# bt_bio.net
KiCad netlist of a schematic drawn in EAGLE
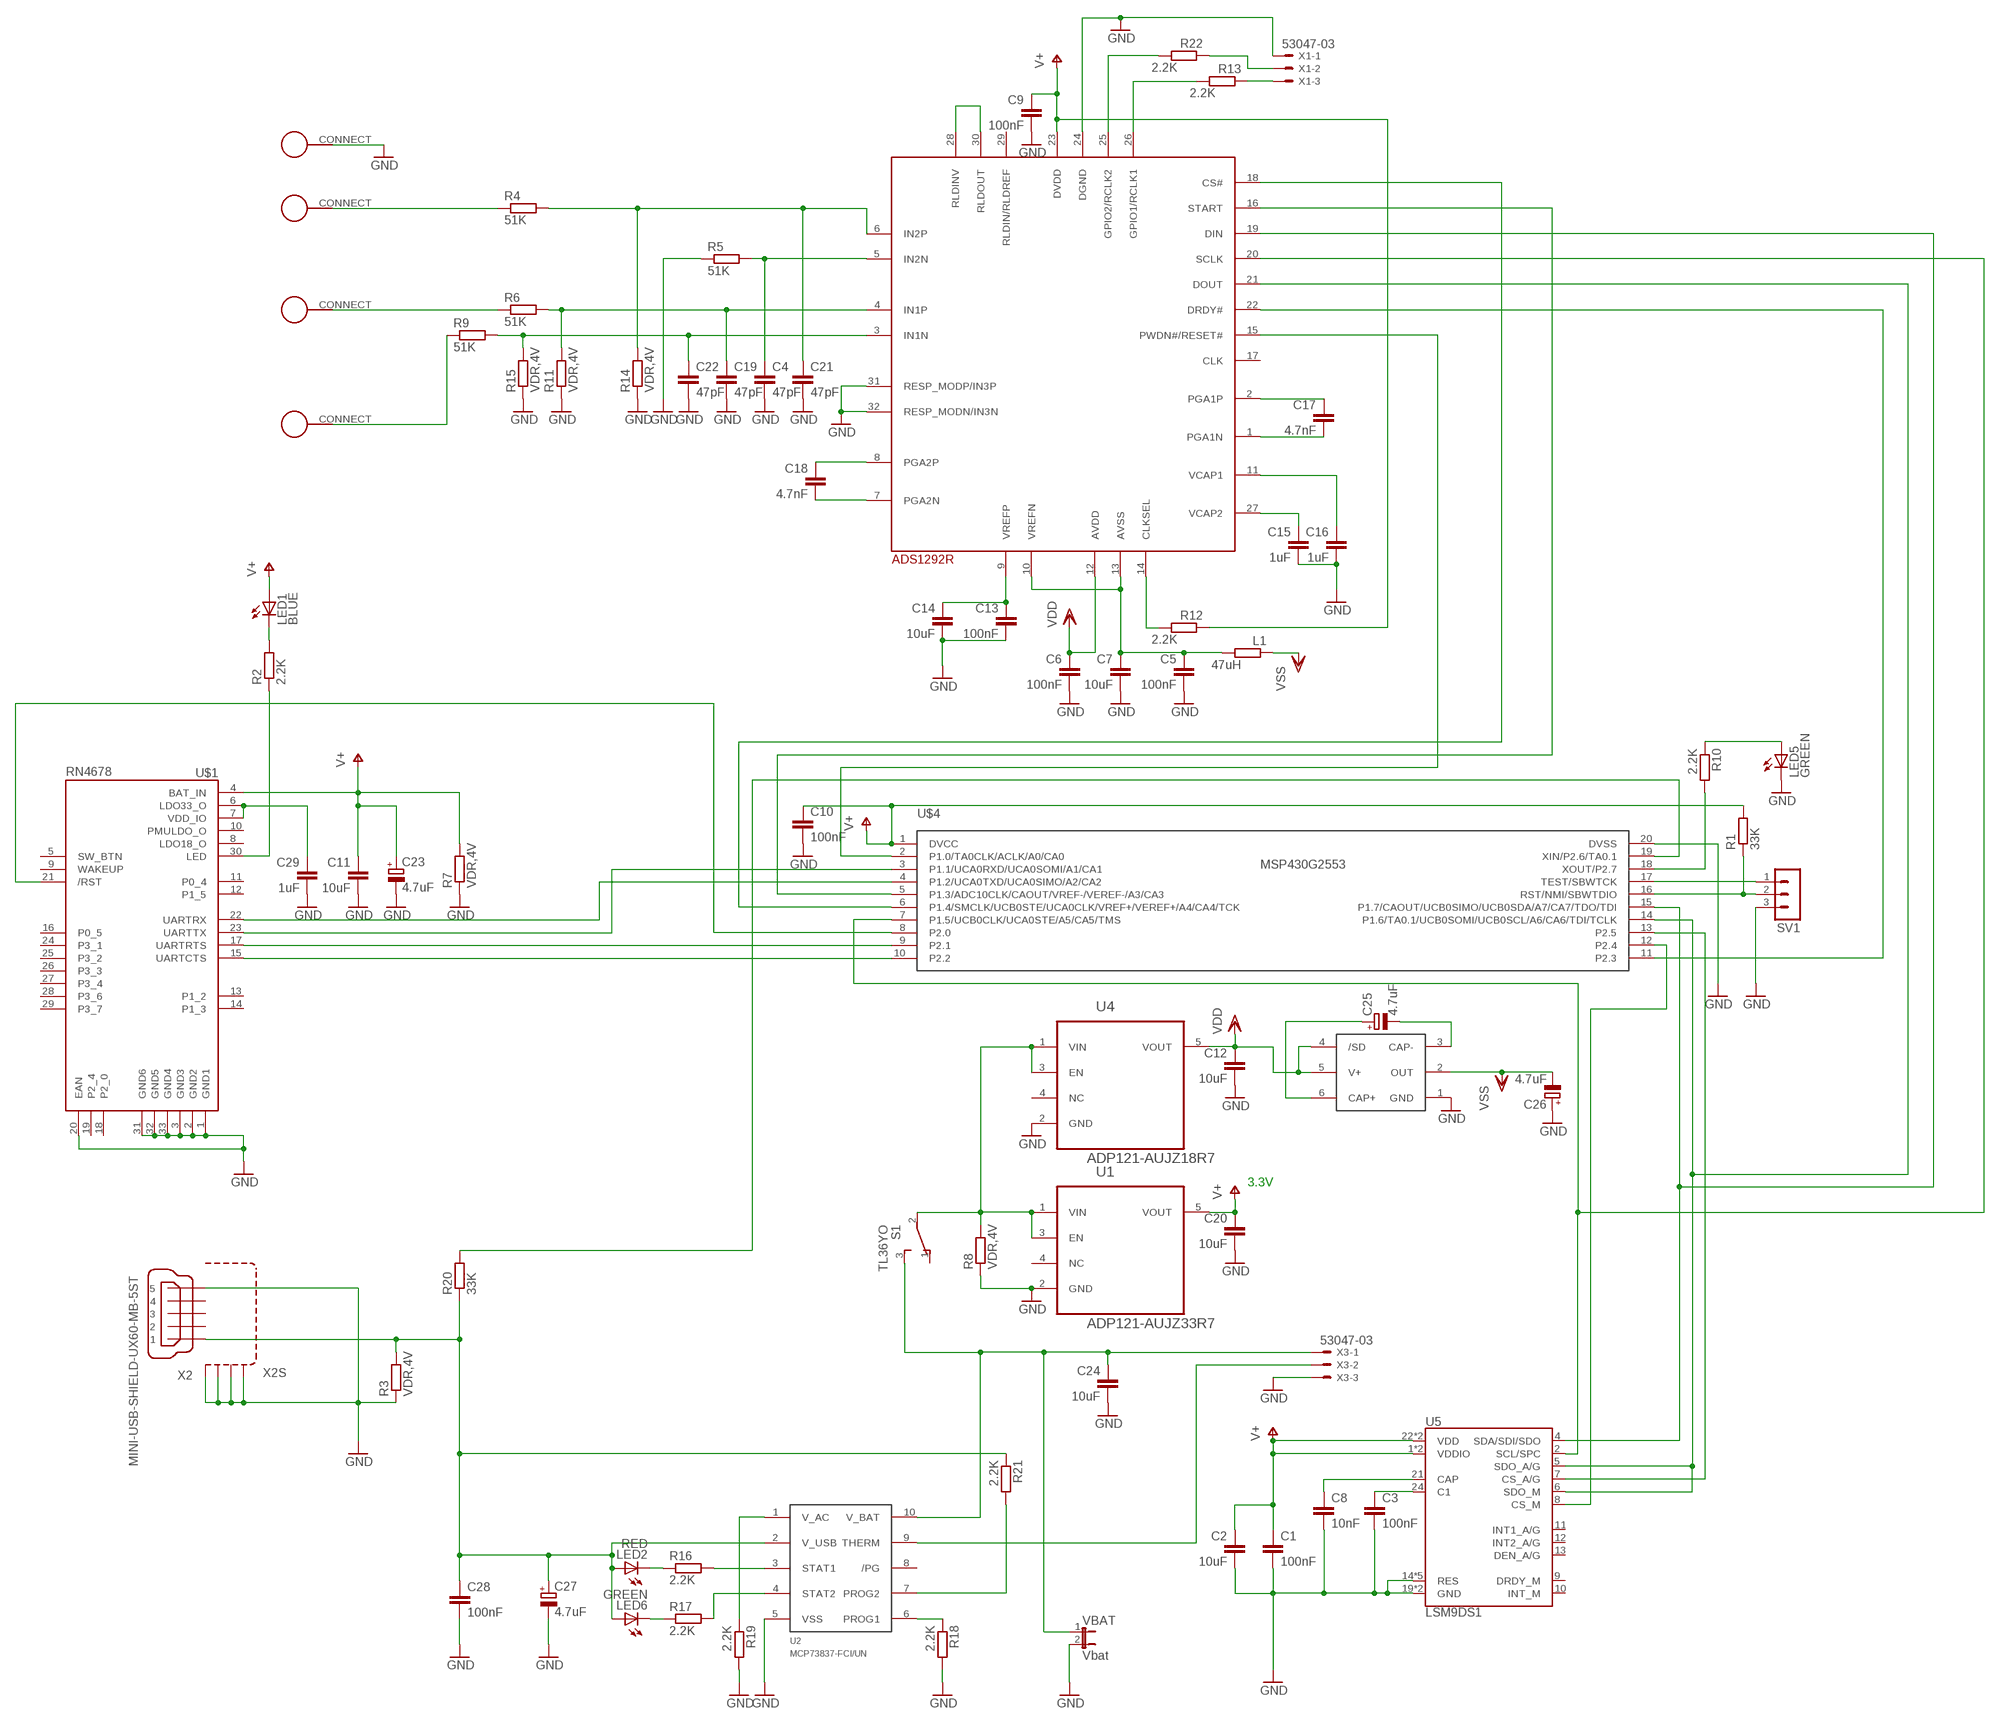
[diagram p0: schematic, sheet 1]

(export (version "E")
  (design (tool "Eeschema 10.0.6"))
  (components
    (comp (ref "ADS1292R")
      (value "ADS1292R")
      (footprint "eagle-import:TQFP-32")
      (libsource (lib "eagle-import") (part "ADS1292R"))
    )
    (comp (ref "C1")
      (value "100nF")
      (footprint "eagle-import:C0603")
      (libsource (lib "eagle-import") (part "C-EUC0603"))
    )
    (comp (ref "C2")
      (value "10uF")
      (footprint "eagle-import:C1206")
      (libsource (lib "eagle-import") (part "C-EUC1206"))
    )
    (comp (ref "C3")
      (value "100nF")
      (footprint "eagle-import:C0603")
      (libsource (lib "eagle-import") (part "C-EUC0603"))
    )
    (comp (ref "C4")
      (value "47pF")
      (footprint "eagle-import:C0603")
      (libsource (lib "eagle-import") (part "C-EUC0603"))
    )
    (comp (ref "C5")
      (value "100nF")
      (footprint "eagle-import:C0603")
      (libsource (lib "eagle-import") (part "C-EUC0603"))
    )
    (comp (ref "C6")
      (value "100nF")
      (footprint "eagle-import:C0603")
      (libsource (lib "eagle-import") (part "C-EUC0603"))
    )
    (comp (ref "C7")
      (value "10uF")
      (footprint "eagle-import:C1206")
      (libsource (lib "eagle-import") (part "C-EUC1206"))
    )
    (comp (ref "C8")
      (value "10nF")
      (footprint "eagle-import:C0603")
      (libsource (lib "eagle-import") (part "C-EUC0603"))
    )
    (comp (ref "C9")
      (value "100nF")
      (footprint "eagle-import:C0603")
      (libsource (lib "eagle-import") (part "C-EUC0603"))
    )
    (comp (ref "C10")
      (value "100nF")
      (footprint "eagle-import:C0603")
      (libsource (lib "eagle-import") (part "C-EUC0603"))
    )
    (comp (ref "C11")
      (value "10uF")
      (footprint "eagle-import:C1206")
      (libsource (lib "eagle-import") (part "C-EUC1206"))
    )
    (comp (ref "C12")
      (value "10uF")
      (footprint "eagle-import:C1206")
      (libsource (lib "eagle-import") (part "C-EUC1206"))
    )
    (comp (ref "C13")
      (value "100nF")
      (footprint "eagle-import:C0603")
      (libsource (lib "eagle-import") (part "C-EUC0603"))
    )
    (comp (ref "C14")
      (value "10uF")
      (footprint "eagle-import:C1206")
      (libsource (lib "eagle-import") (part "C-EUC1206"))
    )
    (comp (ref "C15")
      (value "1uF")
      (footprint "eagle-import:C0603")
      (libsource (lib "eagle-import") (part "C-EUC0603"))
    )
    (comp (ref "C16")
      (value "1uF")
      (footprint "eagle-import:C0603")
      (libsource (lib "eagle-import") (part "C-EUC0603"))
    )
    (comp (ref "C17")
      (value "4.7nF")
      (footprint "eagle-import:C0603")
      (libsource (lib "eagle-import") (part "C-EUC0603"))
    )
    (comp (ref "C18")
      (value "4.7nF")
      (footprint "eagle-import:C0603")
      (libsource (lib "eagle-import") (part "C-EUC0603"))
    )
    (comp (ref "C19")
      (value "47pF")
      (footprint "eagle-import:C0603")
      (libsource (lib "eagle-import") (part "C-EUC0603"))
    )
    (comp (ref "C20")
      (value "10uF")
      (footprint "eagle-import:C1206")
      (libsource (lib "eagle-import") (part "C-EUC1206"))
    )
    (comp (ref "C21")
      (value "47pF")
      (footprint "eagle-import:C0603")
      (libsource (lib "eagle-import") (part "C-EUC0603"))
    )
    (comp (ref "C22")
      (value "47pF")
      (footprint "eagle-import:C0603")
      (libsource (lib "eagle-import") (part "C-EUC0603"))
    )
    (comp (ref "C23")
      (value "4.7uF")
      (footprint "eagle-import:SMC_C")
      (libsource (lib "eagle-import") (part "CPOL-EUSMCC"))
    )
    (comp (ref "C24")
      (value "10uF")
      (footprint "eagle-import:C1206")
      (libsource (lib "eagle-import") (part "C-EUC1206"))
    )
    (comp (ref "C25")
      (value "4.7uF")
      (footprint "eagle-import:SMC_C")
      (libsource (lib "eagle-import") (part "CPOL-EUSMCC"))
    )
    (comp (ref "C26")
      (value "4.7uF")
      (footprint "eagle-import:SMC_C")
      (libsource (lib "eagle-import") (part "CPOL-EUSMCC"))
    )
    (comp (ref "C27")
      (value "4.7uF")
      (footprint "eagle-import:SMC_C")
      (libsource (lib "eagle-import") (part "CPOL-EUSMCC"))
    )
    (comp (ref "C28")
      (value "100nF")
      (footprint "eagle-import:C0603")
      (libsource (lib "eagle-import") (part "C-EUC0603"))
    )
    (comp (ref "C29")
      (value "1uF")
      (footprint "eagle-import:C0603")
      (libsource (lib "eagle-import") (part "C-EUC0603"))
    )
    (comp (ref "L1")
      (value "47uH")
      (footprint "eagle-import:R0805")
      (libsource (lib "eagle-import") (part "R-EU_R0805"))
    )
    (comp (ref "LED1")
      (value "BLUE")
      (footprint "eagle-import:CHIPLED_0805")
      (libsource (lib "eagle-import") (part "LEDCHIPLED_0805"))
    )
    (comp (ref "LED2")
      (value "RED")
      (footprint "eagle-import:CHIPLED_0805")
      (libsource (lib "eagle-import") (part "LEDCHIPLED_0805"))
    )
    (comp (ref "LED5")
      (value "GREEN")
      (footprint "eagle-import:CHIPLED_0805")
      (libsource (lib "eagle-import") (part "LEDCHIPLED_0805"))
    )
    (comp (ref "LED6")
      (value "GREEN")
      (footprint "eagle-import:CHIPLED_0805")
      (libsource (lib "eagle-import") (part "LEDCHIPLED_0805"))
    )
    (comp (ref "R1")
      (value "33K")
      (footprint "eagle-import:R0603")
      (libsource (lib "eagle-import") (part "resistor_R-EU_R0603"))
    )
    (comp (ref "R2")
      (value "2.2K")
      (footprint "eagle-import:R0603")
      (libsource (lib "eagle-import") (part "R-EU_R0603"))
    )
    (comp (ref "R3")
      (value "VDR,4V")
      (footprint "eagle-import:R0805")
      (libsource (lib "eagle-import") (part "R-EU_R0805"))
    )
    (comp (ref "R4")
      (value "51K")
      (footprint "eagle-import:R0603")
      (libsource (lib "eagle-import") (part "R-EU_R0603"))
    )
    (comp (ref "R5")
      (value "51K")
      (footprint "eagle-import:R0603")
      (libsource (lib "eagle-import") (part "R-EU_R0603"))
    )
    (comp (ref "R6")
      (value "51K")
      (footprint "eagle-import:R0603")
      (libsource (lib "eagle-import") (part "R-EU_R0603"))
    )
    (comp (ref "R7")
      (value "VDR,4V")
      (footprint "eagle-import:R0805")
      (libsource (lib "eagle-import") (part "R-EU_R0805"))
    )
    (comp (ref "R8")
      (value "VDR,4V")
      (footprint "eagle-import:R0805")
      (libsource (lib "eagle-import") (part "R-EU_R0805"))
    )
    (comp (ref "R9")
      (value "51K")
      (footprint "eagle-import:R0603")
      (libsource (lib "eagle-import") (part "R-EU_R0603"))
    )
    (comp (ref "R10")
      (value "2.2K")
      (footprint "eagle-import:R0603")
      (libsource (lib "eagle-import") (part "R-EU_R0603"))
    )
    (comp (ref "R11")
      (value "VDR,4V")
      (footprint "eagle-import:R0805")
      (libsource (lib "eagle-import") (part "R-EU_R0805"))
    )
    (comp (ref "R12")
      (value "2.2K")
      (footprint "eagle-import:R0603")
      (libsource (lib "eagle-import") (part "R-EU_R0603"))
    )
    (comp (ref "R13")
      (value "2.2K")
      (footprint "eagle-import:R0603")
      (libsource (lib "eagle-import") (part "R-EU_R0603"))
    )
    (comp (ref "R14")
      (value "VDR,4V")
      (footprint "eagle-import:R0805")
      (libsource (lib "eagle-import") (part "R-EU_R0805"))
    )
    (comp (ref "R15")
      (value "VDR,4V")
      (footprint "eagle-import:R0805")
      (libsource (lib "eagle-import") (part "R-EU_R0805"))
    )
    (comp (ref "R16")
      (value "2.2K")
      (footprint "eagle-import:R0603")
      (libsource (lib "eagle-import") (part "R-EU_R0603"))
    )
    (comp (ref "R17")
      (value "2.2K")
      (footprint "eagle-import:R0603")
      (libsource (lib "eagle-import") (part "R-EU_R0603"))
    )
    (comp (ref "R18")
      (value "2.2K")
      (footprint "eagle-import:R0603")
      (libsource (lib "eagle-import") (part "R-EU_R0603"))
    )
    (comp (ref "R19")
      (value "2.2K")
      (footprint "eagle-import:R0603")
      (libsource (lib "eagle-import") (part "R-EU_R0603"))
    )
    (comp (ref "R20")
      (value "33K")
      (footprint "eagle-import:R0603")
      (libsource (lib "eagle-import") (part "resistor_R-EU_R0603"))
    )
    (comp (ref "R21")
      (value "2.2K")
      (footprint "eagle-import:R0603")
      (libsource (lib "eagle-import") (part "R-EU_R0603"))
    )
    (comp (ref "R22")
      (value "2.2K")
      (footprint "eagle-import:R0603")
      (libsource (lib "eagle-import") (part "R-EU_R0603"))
    )
    (comp (ref "S1")
      (value "TL36YO")
      (footprint "eagle-import:TL3XYO")
      (libsource (lib "eagle-import") (part "TL36YO"))
    )
    (comp (ref "SV1")
      (value "MA03-1")
      (footprint "eagle-import:MA03-1")
      (libsource (lib "eagle-import") (part "MA03-1"))
    )
    (comp (ref "U$1")
      (value "RN4678")
      (footprint "eagle-import:RN4678")
      (libsource (lib "eagle-import") (part "RN4678"))
    )
    (comp (ref "U$4")
      (value "MSP430G2553")
      (footprint "eagle-import:TSSOP20")
      (libsource (lib "eagle-import") (part "MSP430G2553"))
    )
    (comp (ref "U$5")
      (value "4MMCONNECT")
      (footprint "eagle-import:4MMCONNECT")
      (libsource (lib "eagle-import") (part "4MMCONNECT"))
    )
    (comp (ref "U$7")
      (value "4MMCONNECT")
      (footprint "eagle-import:4MMCONNECT")
      (libsource (lib "eagle-import") (part "4MMCONNECT"))
    )
    (comp (ref "U$9")
      (value "4MMCONNECT")
      (footprint "eagle-import:4MMCONNECT")
      (libsource (lib "eagle-import") (part "4MMCONNECT"))
    )
    (comp (ref "U$10")
      (value "4MMCONNECT")
      (footprint "eagle-import:4MMCONNECT")
      (libsource (lib "eagle-import") (part "4MMCONNECT"))
    )
    (comp (ref "U$12")
      (value "LM2664")
      (footprint "eagle-import:SOT-23-5")
      (libsource (lib "eagle-import") (part "LM2664"))
    )
    (comp (ref "U1")
      (value "ADP121-AUJZ33R7")
      (footprint "eagle-import:SOT95P280X100-5N")
      (libsource (lib "eagle-import") (part "ADP121-AUJZ33R7"))
    )
    (comp (ref "U2")
      (value "MCP73837-FCI/UN")
      (footprint "eagle-import:MSOP10")
      (libsource (lib "eagle-import") (part "MCP73837"))
    )
    (comp (ref "U4")
      (value "ADP121-AUJZ18R7")
      (footprint "eagle-import:SOT95P280X100-5N")
      (fields (field (name "MPN") "ADP121-AUJZ33R7"))
      (libsource (lib "eagle-import") (part "ADP121-AUJZ33R7"))
    )
    (comp (ref "U5")
      (value "LSM9DS1")
      (footprint "eagle-import:LGA24-8X4")
      (libsource (lib "eagle-import") (part "LSM9DS1"))
    )
    (comp (ref "VBAT")
      (value "Vbat")
      (footprint "eagle-import:JP1")
      (libsource (lib "eagle-import") (part "JP1E"))
    )
    (comp (ref "X1")
      (value "53047-03")
      (footprint "eagle-import:53047-03")
      (fields (field (name "MPN") "530470310"))
      (libsource (lib "eagle-import") (part "53?-03047"))
    )
    (comp (ref "X2")
      (value "MINI-USB-SHIELD-UX60-MB-5ST")
      (footprint "eagle-import:UX60-MB-5ST")
      (libsource (lib "eagle-import") (part "MINI-USB-SHIELD-UX60-MB-5ST"))
    )
    (comp (ref "X3")
      (value "53047-03")
      (footprint "eagle-import:53047-03")
      (fields (field (name "MPN") "530470310"))
      (libsource (lib "eagle-import") (part "53?-03047"))
    )
  )
  (nets
    (net (code "1") (name "GND") (class "Default")
      (node (ref "ADS1292R") (pin "24") (pinfunction "DGND_24") (pintype "bidirectional"))
      (node (ref "ADS1292R") (pin "31") (pinfunction "RESP_MODP/IN3P_31") (pintype "bidirectional"))
      (node (ref "ADS1292R") (pin "32") (pinfunction "RESP_MODN/IN3N_32") (pintype "bidirectional"))
      (node (ref "C1") (pin "2") (pinfunction "2_2") (pintype "passive"))
      (node (ref "C10") (pin "2") (pinfunction "2_2") (pintype "passive"))
      (node (ref "C11") (pin "2") (pinfunction "2_2") (pintype "passive"))
      (node (ref "C12") (pin "2") (pinfunction "2_2") (pintype "passive"))
      (node (ref "C13") (pin "2") (pinfunction "2_2") (pintype "passive"))
      (node (ref "C14") (pin "2") (pinfunction "2_2") (pintype "passive"))
      (node (ref "C15") (pin "2") (pinfunction "2_2") (pintype "passive"))
      (node (ref "C16") (pin "2") (pinfunction "2_2") (pintype "passive"))
      (node (ref "C19") (pin "2") (pinfunction "2_2") (pintype "passive"))
      (node (ref "C2") (pin "2") (pinfunction "2_2") (pintype "passive"))
      (node (ref "C20") (pin "2") (pinfunction "2_2") (pintype "passive"))
      (node (ref "C21") (pin "2") (pinfunction "2_2") (pintype "passive"))
      (node (ref "C22") (pin "2") (pinfunction "2_2") (pintype "passive"))
      (node (ref "C23") (pin "-") (pinfunction "-_-") (pintype "passive"))
      (node (ref "C24") (pin "2") (pinfunction "2_2") (pintype "passive"))
      (node (ref "C26") (pin "+") (pinfunction "+_+") (pintype "passive"))
      (node (ref "C27") (pin "-") (pinfunction "-_-") (pintype "passive"))
      (node (ref "C28") (pin "2") (pinfunction "2_2") (pintype "passive"))
      (node (ref "C29") (pin "2") (pinfunction "2_2") (pintype "passive"))
      (node (ref "C3") (pin "2") (pinfunction "2_2") (pintype "passive"))
      (node (ref "C4") (pin "2") (pinfunction "2_2") (pintype "passive"))
      (node (ref "C5") (pin "2") (pinfunction "2_2") (pintype "passive"))
      (node (ref "C6") (pin "2") (pinfunction "2_2") (pintype "passive"))
      (node (ref "C7") (pin "2") (pinfunction "2_2") (pintype "passive"))
      (node (ref "C8") (pin "2") (pinfunction "2_2") (pintype "passive"))
      (node (ref "C9") (pin "2") (pinfunction "2_2") (pintype "passive"))
      (node (ref "LED5") (pin "C") (pinfunction "C_C") (pintype "passive"))
      (node (ref "R11") (pin "1") (pinfunction "1_1") (pintype "passive"))
      (node (ref "R14") (pin "1") (pinfunction "1_1") (pintype "passive"))
      (node (ref "R15") (pin "1") (pinfunction "1_1") (pintype "passive"))
      (node (ref "R18") (pin "2") (pinfunction "2_2") (pintype "passive"))
      (node (ref "R19") (pin "2") (pinfunction "2_2") (pintype "passive"))
      (node (ref "R3") (pin "1") (pinfunction "1_1") (pintype "passive"))
      (node (ref "R5") (pin "1") (pinfunction "1_1") (pintype "passive"))
      (node (ref "R7") (pin "1") (pinfunction "1_1") (pintype "passive"))
      (node (ref "R8") (pin "1") (pinfunction "1_1") (pintype "passive"))
      (node (ref "SV1") (pin "3") (pinfunction "3_3") (pintype "passive"))
      (node (ref "U$1") (pin "1") (pinfunction "GND1_1") (pintype "bidirectional"))
      (node (ref "U$1") (pin "2") (pinfunction "GND2_2") (pintype "bidirectional"))
      (node (ref "U$1") (pin "20") (pinfunction "EAN_20") (pintype "bidirectional"))
      (node (ref "U$1") (pin "3") (pinfunction "GND3_3") (pintype "bidirectional"))
      (node (ref "U$1") (pin "31") (pinfunction "GND6_31") (pintype "bidirectional"))
      (node (ref "U$1") (pin "32") (pinfunction "GND5_32") (pintype "bidirectional"))
      (node (ref "U$1") (pin "33") (pinfunction "GND4_33") (pintype "bidirectional"))
      (node (ref "U$12") (pin "1") (pinfunction "GND_1") (pintype "power_in"))
      (node (ref "U$4") (pin "20") (pinfunction "DVSS_20") (pintype "bidirectional"))
      (node (ref "U$5") (pin "CONNECT") (pinfunction "CONNECT_CONNECT") (pintype "passive"))
      (node (ref "U1") (pin "2") (pinfunction "GND_2") (pintype "passive"))
      (node (ref "U2") (pin "5") (pinfunction "VSS_5") (pintype "bidirectional"))
      (node (ref "U4") (pin "2") (pinfunction "GND_2") (pintype "passive"))
      (node (ref "U5") (pin "14") (pinfunction "RES_14") (pintype "bidirectional"))
      (node (ref "U5") (pin "15") (pinfunction "RES_15") (pintype "bidirectional"))
      (node (ref "U5") (pin "16") (pinfunction "RES_16") (pintype "bidirectional"))
      (node (ref "U5") (pin "17") (pinfunction "RES_17") (pintype "bidirectional"))
      (node (ref "U5") (pin "18") (pinfunction "RES_18") (pintype "bidirectional"))
      (node (ref "U5") (pin "19") (pinfunction "GND_19") (pintype "bidirectional"))
      (node (ref "U5") (pin "20") (pinfunction "GND_20") (pintype "bidirectional"))
      (node (ref "VBAT") (pin "2") (pinfunction "2_2") (pintype "passive"))
      (node (ref "X1") (pin "1") (pinfunction "S_1") (pintype "passive"))
      (node (ref "X2") (pin "5") (pinfunction "5_5") (pintype "input"))
      (node (ref "X2") (pin "M1") (pinfunction "S1_M1") (pintype "passive"))
      (node (ref "X2") (pin "M2") (pinfunction "S2_M2") (pintype "passive"))
      (node (ref "X2") (pin "M3") (pinfunction "S3_M3") (pintype "passive"))
      (node (ref "X2") (pin "M4") (pinfunction "S4_M4") (pintype "passive"))
      (node (ref "X3") (pin "3") (pinfunction "S_3") (pintype "passive"))
    )
    (net (code "2") (name "Net-(ADS1292R-AVSS)") (class "Default")
      (node (ref "ADS1292R") (pin "10") (pinfunction "VREFN_10") (pintype "bidirectional"))
      (node (ref "ADS1292R") (pin "13") (pinfunction "AVSS_13") (pintype "bidirectional"))
      (node (ref "C5") (pin "1") (pinfunction "1_1") (pintype "passive"))
      (node (ref "C7") (pin "1") (pinfunction "1_1") (pintype "passive"))
      (node (ref "L1") (pin "2") (pinfunction "2_2") (pintype "passive"))
    )
    (net (code "3") (name "Net-(ADS1292R-CLKSEL)") (class "Default")
      (node (ref "ADS1292R") (pin "14") (pinfunction "CLKSEL_14") (pintype "bidirectional"))
      (node (ref "R12") (pin "2") (pinfunction "2_2") (pintype "passive"))
    )
    (net (code "4") (name "Net-(ADS1292R-CS#)") (class "Default")
      (node (ref "ADS1292R") (pin "18") (pinfunction "CS#_18") (pintype "bidirectional"))
      (node (ref "U$4") (pin "6") (pinfunction "P1.4/SMCLK/UCB0STE/UCA0CLK/VREF+/VEREF+/A4/CA4/TCK_6") (pintype "bidirectional"))
    )
    (net (code "5") (name "Net-(ADS1292R-DIN)") (class "Default")
      (node (ref "ADS1292R") (pin "19") (pinfunction "DIN_19") (pintype "bidirectional"))
      (node (ref "U$4") (pin "15") (pinfunction "P1.7/CAOUT/UCB0SIMO/UCB0SDA/A7/CA7/TDO/TDI_15") (pintype "bidirectional"))
      (node (ref "U5") (pin "4") (pinfunction "SDA/SDI/SDO_4") (pintype "bidirectional"))
    )
    (net (code "6") (name "Net-(ADS1292R-DOUT)") (class "Default")
      (node (ref "ADS1292R") (pin "21") (pinfunction "DOUT_21") (pintype "bidirectional"))
      (node (ref "U$4") (pin "14") (pinfunction "P1.6/TA0.1/UCB0SOMI/UCB0SCL/A6/CA6/TDI/TCLK_14") (pintype "bidirectional"))
      (node (ref "U5") (pin "5") (pinfunction "SDO_A/G_5") (pintype "bidirectional"))
      (node (ref "U5") (pin "6") (pinfunction "SDO_M_6") (pintype "bidirectional"))
    )
    (net (code "7") (name "Net-(ADS1292R-DRDY#)") (class "Default")
      (node (ref "ADS1292R") (pin "22") (pinfunction "DRDY#_22") (pintype "bidirectional"))
      (node (ref "U$4") (pin "11") (pinfunction "P2.3_11") (pintype "bidirectional"))
    )
    (net (code "8") (name "Net-(ADS1292R-GPIO1{slash}RCLK1)") (class "Default")
      (node (ref "ADS1292R") (pin "26") (pinfunction "GPIO1/RCLK1_26") (pintype "bidirectional"))
      (node (ref "R13") (pin "2") (pinfunction "2_2") (pintype "passive"))
    )
    (net (code "9") (name "Net-(ADS1292R-GPIO2{slash}RCLK2)") (class "Default")
      (node (ref "ADS1292R") (pin "25") (pinfunction "GPIO2/RCLK2_25") (pintype "bidirectional"))
      (node (ref "R22") (pin "2") (pinfunction "2_2") (pintype "passive"))
    )
    (net (code "10") (name "Net-(ADS1292R-IN1N)") (class "Default")
      (node (ref "ADS1292R") (pin "3") (pinfunction "IN1N_3") (pintype "bidirectional"))
      (node (ref "C22") (pin "1") (pinfunction "1_1") (pintype "passive"))
      (node (ref "R15") (pin "2") (pinfunction "2_2") (pintype "passive"))
      (node (ref "R9") (pin "2") (pinfunction "2_2") (pintype "passive"))
    )
    (net (code "11") (name "Net-(ADS1292R-IN1P)") (class "Default")
      (node (ref "ADS1292R") (pin "4") (pinfunction "IN1P_4") (pintype "bidirectional"))
      (node (ref "C19") (pin "1") (pinfunction "1_1") (pintype "passive"))
      (node (ref "R11") (pin "2") (pinfunction "2_2") (pintype "passive"))
      (node (ref "R6") (pin "2") (pinfunction "2_2") (pintype "passive"))
    )
    (net (code "12") (name "Net-(ADS1292R-IN2N)") (class "Default")
      (node (ref "ADS1292R") (pin "5") (pinfunction "IN2N_5") (pintype "bidirectional"))
      (node (ref "C4") (pin "1") (pinfunction "1_1") (pintype "passive"))
      (node (ref "R5") (pin "2") (pinfunction "2_2") (pintype "passive"))
    )
    (net (code "13") (name "Net-(ADS1292R-IN2P)") (class "Default")
      (node (ref "ADS1292R") (pin "6") (pinfunction "IN2P_6") (pintype "bidirectional"))
      (node (ref "C21") (pin "1") (pinfunction "1_1") (pintype "passive"))
      (node (ref "R14") (pin "2") (pinfunction "2_2") (pintype "passive"))
      (node (ref "R4") (pin "2") (pinfunction "2_2") (pintype "passive"))
    )
    (net (code "14") (name "Net-(ADS1292R-PGA1N)") (class "Default")
      (node (ref "ADS1292R") (pin "1") (pinfunction "PGA1N_1") (pintype "bidirectional"))
      (node (ref "C17") (pin "2") (pinfunction "2_2") (pintype "passive"))
    )
    (net (code "15") (name "Net-(ADS1292R-PGA1P)") (class "Default")
      (node (ref "ADS1292R") (pin "2") (pinfunction "PGA1P_2") (pintype "bidirectional"))
      (node (ref "C17") (pin "1") (pinfunction "1_1") (pintype "passive"))
    )
    (net (code "16") (name "Net-(ADS1292R-PGA2N)") (class "Default")
      (node (ref "ADS1292R") (pin "7") (pinfunction "PGA2N_7") (pintype "bidirectional"))
      (node (ref "C18") (pin "2") (pinfunction "2_2") (pintype "passive"))
    )
    (net (code "17") (name "Net-(ADS1292R-PGA2P)") (class "Default")
      (node (ref "ADS1292R") (pin "8") (pinfunction "PGA2P_8") (pintype "bidirectional"))
      (node (ref "C18") (pin "1") (pinfunction "1_1") (pintype "passive"))
    )
    (net (code "18") (name "Net-(ADS1292R-PWDN#{slash}RESET#)") (class "Default")
      (node (ref "ADS1292R") (pin "15") (pinfunction "PWDN#/RESET#_15") (pintype "bidirectional"))
      (node (ref "U$4") (pin "2") (pinfunction "P1.0/TA0CLK/ACLK/A0/CA0_2") (pintype "bidirectional"))
    )
    (net (code "19") (name "Net-(ADS1292R-RLDINV)") (class "Default")
      (node (ref "ADS1292R") (pin "28") (pinfunction "RLDINV_28") (pintype "bidirectional"))
      (node (ref "ADS1292R") (pin "30") (pinfunction "RLDOUT_30") (pintype "bidirectional"))
    )
    (net (code "20") (name "Net-(ADS1292R-SCLK)") (class "Default")
      (node (ref "ADS1292R") (pin "20") (pinfunction "SCLK_20") (pintype "bidirectional"))
      (node (ref "U$4") (pin "7") (pinfunction "P1.5/UCB0CLK/UCA0STE/A5/CA5/TMS_7") (pintype "bidirectional"))
      (node (ref "U5") (pin "2") (pinfunction "SCL/SPC_2") (pintype "bidirectional"))
    )
    (net (code "21") (name "Net-(ADS1292R-START)") (class "Default")
      (node (ref "ADS1292R") (pin "16") (pinfunction "START_16") (pintype "bidirectional"))
      (node (ref "U$4") (pin "5") (pinfunction "P1.3/ADC10CLK/CAOUT/VREF-/VEREF-/A3/CA3_5") (pintype "bidirectional"))
    )
    (net (code "22") (name "Net-(ADS1292R-VCAP1)") (class "Default")
      (node (ref "ADS1292R") (pin "11") (pinfunction "VCAP1_11") (pintype "bidirectional"))
      (node (ref "C16") (pin "1") (pinfunction "1_1") (pintype "passive"))
    )
    (net (code "23") (name "Net-(ADS1292R-VCAP2)") (class "Default")
      (node (ref "ADS1292R") (pin "27") (pinfunction "VCAP2_27") (pintype "bidirectional"))
      (node (ref "C15") (pin "1") (pinfunction "1_1") (pintype "passive"))
    )
    (net (code "24") (name "Net-(ADS1292R-VREFP)") (class "Default")
      (node (ref "ADS1292R") (pin "9") (pinfunction "VREFP_9") (pintype "bidirectional"))
      (node (ref "C13") (pin "1") (pinfunction "1_1") (pintype "passive"))
      (node (ref "C14") (pin "1") (pinfunction "1_1") (pintype "passive"))
    )
    (net (code "25") (name "Net-(LED1-PadC)") (class "Default")
      (node (ref "LED1") (pin "C") (pinfunction "C_C") (pintype "passive"))
      (node (ref "R2") (pin "2") (pinfunction "2_2") (pintype "passive"))
    )
    (net (code "26") (name "Net-(LED2-PadC)") (class "Default")
      (node (ref "LED2") (pin "C") (pinfunction "C_C") (pintype "passive"))
      (node (ref "R16") (pin "1") (pinfunction "1_1") (pintype "passive"))
    )
    (net (code "27") (name "Net-(LED5-PadA)") (class "Default")
      (node (ref "LED5") (pin "A") (pinfunction "A_A") (pintype "passive"))
      (node (ref "R10") (pin "1") (pinfunction "1_1") (pintype "passive"))
    )
    (net (code "28") (name "Net-(LED6-PadC)") (class "Default")
      (node (ref "LED6") (pin "C") (pinfunction "C_C") (pintype "passive"))
      (node (ref "R17") (pin "1") (pinfunction "1_1") (pintype "passive"))
    )
    (net (code "29") (name "Net-(R4-Pad1)") (class "Default")
      (node (ref "R4") (pin "1") (pinfunction "1_1") (pintype "passive"))
      (node (ref "U$7") (pin "CONNECT") (pinfunction "CONNECT_CONNECT") (pintype "passive"))
    )
    (net (code "30") (name "Net-(R6-Pad1)") (class "Default")
      (node (ref "R6") (pin "1") (pinfunction "1_1") (pintype "passive"))
      (node (ref "U$9") (pin "CONNECT") (pinfunction "CONNECT_CONNECT") (pintype "passive"))
    )
    (net (code "31") (name "Net-(R9-Pad1)") (class "Default")
      (node (ref "R9") (pin "1") (pinfunction "1_1") (pintype "passive"))
      (node (ref "U$10") (pin "CONNECT") (pinfunction "CONNECT_CONNECT") (pintype "passive"))
    )
    (net (code "32") (name "Net-(S1-P)") (class "Default")
      (node (ref "R8") (pin "2") (pinfunction "2_2") (pintype "passive"))
      (node (ref "S1") (pin "2") (pinfunction "P_2") (pintype "passive"))
      (node (ref "U1") (pin "1") (pinfunction "VIN_1") (pintype "input"))
      (node (ref "U1") (pin "3") (pinfunction "EN_3") (pintype "input"))
      (node (ref "U4") (pin "1") (pinfunction "VIN_1") (pintype "input"))
      (node (ref "U4") (pin "3") (pinfunction "EN_3") (pintype "input"))
    )
    (net (code "33") (name "Net-(S1-S)") (class "Default")
      (node (ref "C24") (pin "1") (pinfunction "1_1") (pintype "passive"))
      (node (ref "S1") (pin "3") (pinfunction "S_3") (pintype "passive"))
      (node (ref "U2") (pin "10") (pinfunction "V_BAT_10") (pintype "bidirectional"))
      (node (ref "VBAT") (pin "1") (pinfunction "1_1") (pintype "passive"))
      (node (ref "X3") (pin "1") (pinfunction "S_1") (pintype "passive"))
    )
    (net (code "34") (name "Net-(U$1-LDO33_O)") (class "Default")
      (node (ref "C29") (pin "1") (pinfunction "1_1") (pintype "passive"))
      (node (ref "U$1") (pin "6") (pinfunction "LDO33_O_6") (pintype "bidirectional"))
      (node (ref "U$1") (pin "7") (pinfunction "VDD_IO_7") (pintype "bidirectional"))
    )
    (net (code "35") (name "Net-(U$1-LED)") (class "Default")
      (node (ref "R2") (pin "1") (pinfunction "1_1") (pintype "passive"))
      (node (ref "U$1") (pin "30") (pinfunction "LED_30") (pintype "bidirectional"))
    )
    (net (code "36") (name "Net-(U$1-UARTCTS)") (class "Default")
      (node (ref "U$1") (pin "15") (pinfunction "UARTCTS_15") (pintype "bidirectional"))
      (node (ref "U$4") (pin "10") (pinfunction "P2.2_10") (pintype "bidirectional"))
    )
    (net (code "37") (name "Net-(U$1-UARTRTS)") (class "Default")
      (node (ref "U$1") (pin "17") (pinfunction "UARTRTS_17") (pintype "bidirectional"))
      (node (ref "U$4") (pin "9") (pinfunction "P2.1_9") (pintype "bidirectional"))
    )
    (net (code "38") (name "Net-(U$1-UARTRX)") (class "Default")
      (node (ref "U$1") (pin "22") (pinfunction "UARTRX_22") (pintype "bidirectional"))
      (node (ref "U$4") (pin "4") (pinfunction "P1.2/UCA0TXD/UCA0SIMO/A2/CA2_4") (pintype "bidirectional"))
    )
    (net (code "39") (name "Net-(U$1-UARTTX)") (class "Default")
      (node (ref "U$1") (pin "23") (pinfunction "UARTTX_23") (pintype "bidirectional"))
      (node (ref "U$4") (pin "3") (pinfunction "P1.1/UCA0RXD/UCA0SOMI/A1/CA1_3") (pintype "bidirectional"))
    )
    (net (code "40") (name "Net-(U$1-{slash}RST)") (class "Default")
      (node (ref "U$1") (pin "21") (pinfunction "/RST_21") (pintype "bidirectional"))
      (node (ref "U$4") (pin "8") (pinfunction "P2.0_8") (pintype "bidirectional"))
    )
    (net (code "41") (name "Net-(U$4-P2.4)") (class "Default")
      (node (ref "U$4") (pin "12") (pinfunction "P2.4_12") (pintype "bidirectional"))
      (node (ref "U5") (pin "8") (pinfunction "CS_M_8") (pintype "bidirectional"))
    )
    (net (code "42") (name "Net-(U$4-P2.5)") (class "Default")
      (node (ref "U$4") (pin "13") (pinfunction "P2.5_13") (pintype "bidirectional"))
      (node (ref "U5") (pin "7") (pinfunction "CS_A/G_7") (pintype "bidirectional"))
    )
    (net (code "43") (name "Net-(U$4-RST{slash}NMI{slash}SBWTDIO)") (class "Default")
      (node (ref "R1") (pin "1") (pinfunction "1_1") (pintype "passive"))
      (node (ref "SV1") (pin "2") (pinfunction "2_2") (pintype "passive"))
      (node (ref "U$4") (pin "16") (pinfunction "RST/NMI/SBWTDIO_16") (pintype "bidirectional"))
    )
    (net (code "44") (name "Net-(U$4-TEST{slash}SBWTCK)") (class "Default")
      (node (ref "SV1") (pin "1") (pinfunction "1_1") (pintype "passive"))
      (node (ref "U$4") (pin "17") (pinfunction "TEST/SBWTCK_17") (pintype "bidirectional"))
    )
    (net (code "45") (name "Net-(U$4-XIN{slash}P2.6{slash}TA0.1)") (class "Default")
      (node (ref "R20") (pin "2") (pinfunction "2_2") (pintype "passive"))
      (node (ref "U$4") (pin "19") (pinfunction "XIN/P2.6/TA0.1_19") (pintype "bidirectional"))
    )
    (net (code "46") (name "Net-(U$4-XOUT{slash}P2.7)") (class "Default")
      (node (ref "R10") (pin "2") (pinfunction "2_2") (pintype "passive"))
      (node (ref "U$4") (pin "18") (pinfunction "XOUT/P2.7_18") (pintype "bidirectional"))
    )
    (net (code "47") (name "Net-(U$12-CAP+)") (class "Default")
      (node (ref "C25") (pin "+") (pinfunction "+_+") (pintype "passive"))
      (node (ref "U$12") (pin "6") (pinfunction "CAP+_6") (pintype "bidirectional"))
    )
    (net (code "48") (name "Net-(U$12-CAP-)") (class "Default")
      (node (ref "C25") (pin "-") (pinfunction "-_-") (pintype "passive"))
      (node (ref "U$12") (pin "3") (pinfunction "CAP-_3") (pintype "bidirectional"))
    )
    (net (code "49") (name "Net-(U2-PROG1)") (class "Default")
      (node (ref "R18") (pin "1") (pinfunction "1_1") (pintype "passive"))
      (node (ref "U2") (pin "6") (pinfunction "PROG1_6") (pintype "bidirectional"))
    )
    (net (code "50") (name "Net-(U2-PROG2)") (class "Default")
      (node (ref "R21") (pin "2") (pinfunction "2_2") (pintype "passive"))
      (node (ref "U2") (pin "7") (pinfunction "PROG2_7") (pintype "bidirectional"))
    )
    (net (code "51") (name "Net-(U2-STAT1)") (class "Default")
      (node (ref "R16") (pin "2") (pinfunction "2_2") (pintype "passive"))
      (node (ref "U2") (pin "3") (pinfunction "STAT1_3") (pintype "bidirectional"))
    )
    (net (code "52") (name "Net-(U2-STAT2)") (class "Default")
      (node (ref "R17") (pin "2") (pinfunction "2_2") (pintype "passive"))
      (node (ref "U2") (pin "4") (pinfunction "STAT2_4") (pintype "bidirectional"))
    )
    (net (code "53") (name "Net-(U2-THERM)") (class "Default")
      (node (ref "U2") (pin "9") (pinfunction "THERM_9") (pintype "bidirectional"))
      (node (ref "X3") (pin "2") (pinfunction "S_2") (pintype "passive"))
    )
    (net (code "54") (name "Net-(U2-V_AC)") (class "Default")
      (node (ref "R19") (pin "1") (pinfunction "1_1") (pintype "passive"))
      (node (ref "U2") (pin "1") (pinfunction "V_AC_1") (pintype "bidirectional"))
    )
    (net (code "55") (name "Net-(U2-V_USB)") (class "Default")
      (node (ref "C27") (pin "+") (pinfunction "+_+") (pintype "passive"))
      (node (ref "C28") (pin "1") (pinfunction "1_1") (pintype "passive"))
      (node (ref "LED2") (pin "A") (pinfunction "A_A") (pintype "passive"))
      (node (ref "LED6") (pin "A") (pinfunction "A_A") (pintype "passive"))
      (node (ref "R20") (pin "1") (pinfunction "1_1") (pintype "passive"))
      (node (ref "R21") (pin "1") (pinfunction "1_1") (pintype "passive"))
      (node (ref "R3") (pin "2") (pinfunction "2_2") (pintype "passive"))
      (node (ref "U2") (pin "2") (pinfunction "V_USB_2") (pintype "bidirectional"))
      (node (ref "X2") (pin "1") (pinfunction "1_1") (pintype "input"))
    )
    (net (code "56") (name "Net-(U5-C1)") (class "Default")
      (node (ref "C3") (pin "1") (pinfunction "1_1") (pintype "passive"))
      (node (ref "U5") (pin "24") (pinfunction "C1_24") (pintype "bidirectional"))
    )
    (net (code "57") (name "Net-(U5-CAP)") (class "Default")
      (node (ref "C8") (pin "1") (pinfunction "1_1") (pintype "passive"))
      (node (ref "U5") (pin "21") (pinfunction "CAP_21") (pintype "bidirectional"))
    )
    (net (code "58") (name "Net-(X1B-S)") (class "Default")
      (node (ref "R22") (pin "1") (pinfunction "1_1") (pintype "passive"))
      (node (ref "X1") (pin "2") (pinfunction "S_2") (pintype "passive"))
    )
    (net (code "59") (name "Net-(X1C-S)") (class "Default")
      (node (ref "R13") (pin "1") (pinfunction "1_1") (pintype "passive"))
      (node (ref "X1") (pin "3") (pinfunction "S_3") (pintype "passive"))
    )
    (net (code "60") (name "V+") (class "Default")
      (node (ref "ADS1292R") (pin "23") (pinfunction "DVDD_23") (pintype "bidirectional"))
      (node (ref "C1") (pin "1") (pinfunction "1_1") (pintype "passive"))
      (node (ref "C10") (pin "1") (pinfunction "1_1") (pintype "passive"))
      (node (ref "C11") (pin "1") (pinfunction "1_1") (pintype "passive"))
      (node (ref "C2") (pin "1") (pinfunction "1_1") (pintype "passive"))
      (node (ref "C20") (pin "1") (pinfunction "1_1") (pintype "passive"))
      (node (ref "C23") (pin "+") (pinfunction "+_+") (pintype "passive"))
      (node (ref "C9") (pin "1") (pinfunction "1_1") (pintype "passive"))
      (node (ref "LED1") (pin "A") (pinfunction "A_A") (pintype "passive"))
      (node (ref "R1") (pin "2") (pinfunction "2_2") (pintype "passive"))
      (node (ref "R12") (pin "1") (pinfunction "1_1") (pintype "passive"))
      (node (ref "R7") (pin "2") (pinfunction "2_2") (pintype "passive"))
      (node (ref "U$1") (pin "4") (pinfunction "BAT_IN_4") (pintype "bidirectional"))
      (node (ref "U$4") (pin "1") (pinfunction "DVCC_1") (pintype "bidirectional"))
      (node (ref "U1") (pin "5") (pinfunction "VOUT_5") (pintype "output"))
      (node (ref "U5") (pin "1") (pinfunction "VDDIO_1") (pintype "bidirectional"))
      (node (ref "U5") (pin "22") (pinfunction "VDD_22") (pintype "bidirectional"))
      (node (ref "U5") (pin "23") (pinfunction "VDD_23") (pintype "bidirectional"))
      (node (ref "U5") (pin "3") (pinfunction "VDDIO_3") (pintype "bidirectional"))
    )
    (net (code "61") (name "VDD") (class "Default")
      (node (ref "ADS1292R") (pin "12") (pinfunction "AVDD_12") (pintype "bidirectional"))
      (node (ref "C12") (pin "1") (pinfunction "1_1") (pintype "passive"))
      (node (ref "C6") (pin "1") (pinfunction "1_1") (pintype "passive"))
      (node (ref "U$12") (pin "4") (pinfunction "/SD_4") (pintype "bidirectional"))
      (node (ref "U$12") (pin "5") (pinfunction "V+_5") (pintype "power_in"))
      (node (ref "U4") (pin "5") (pinfunction "VOUT_5") (pintype "output"))
    )
    (net (code "62") (name "VSS") (class "Default")
      (node (ref "C26") (pin "-") (pinfunction "-_-") (pintype "passive"))
      (node (ref "L1") (pin "1") (pinfunction "1_1") (pintype "passive"))
      (node (ref "U$12") (pin "2") (pinfunction "OUT_2") (pintype "bidirectional"))
    )
    (net (code "63") (name "unconnected-(ADS1292R-CLK-Pad17)") (class "Default")
      (node (ref "ADS1292R") (pin "17") (pinfunction "CLK_17") (pintype "bidirectional"))
    )
    (net (code "64") (name "unconnected-(ADS1292R-RLDIN{slash}RLDREF-Pad29)") (class "Default")
      (node (ref "ADS1292R") (pin "29") (pinfunction "RLDIN/RLDREF_29") (pintype "bidirectional"))
    )
    (net (code "65") (name "unconnected-(S1-O-Pad1)") (class "Default")
      (node (ref "S1") (pin "1") (pinfunction "O_1") (pintype "passive"))
    )
    (net (code "66") (name "unconnected-(U$1-LDO18_O-Pad8)") (class "Default")
      (node (ref "U$1") (pin "8") (pinfunction "LDO18_O_8") (pintype "bidirectional"))
    )
    (net (code "67") (name "unconnected-(U$1-P0_4-Pad11)") (class "Default")
      (node (ref "U$1") (pin "11") (pinfunction "P0_4_11") (pintype "bidirectional"))
    )
    (net (code "68") (name "unconnected-(U$1-P0_5-Pad16)") (class "Default")
      (node (ref "U$1") (pin "16") (pinfunction "P0_5_16") (pintype "bidirectional"))
    )
    (net (code "69") (name "unconnected-(U$1-P1_2-Pad13)") (class "Default")
      (node (ref "U$1") (pin "13") (pinfunction "P1_2_13") (pintype "bidirectional"))
    )
    (net (code "70") (name "unconnected-(U$1-P1_3-Pad14)") (class "Default")
      (node (ref "U$1") (pin "14") (pinfunction "P1_3_14") (pintype "bidirectional"))
    )
    (net (code "71") (name "unconnected-(U$1-P1_5-Pad12)") (class "Default")
      (node (ref "U$1") (pin "12") (pinfunction "P1_5_12") (pintype "bidirectional"))
    )
    (net (code "72") (name "unconnected-(U$1-P2_0-Pad18)") (class "Default")
      (node (ref "U$1") (pin "18") (pinfunction "P2_0_18") (pintype "bidirectional"))
    )
    (net (code "73") (name "unconnected-(U$1-P2_4-Pad19)") (class "Default")
      (node (ref "U$1") (pin "19") (pinfunction "P2_4_19") (pintype "bidirectional"))
    )
    (net (code "74") (name "unconnected-(U$1-P3_1-Pad24)") (class "Default")
      (node (ref "U$1") (pin "24") (pinfunction "P3_1_24") (pintype "bidirectional"))
    )
    (net (code "75") (name "unconnected-(U$1-P3_2-Pad25)") (class "Default")
      (node (ref "U$1") (pin "25") (pinfunction "P3_2_25") (pintype "bidirectional"))
    )
    (net (code "76") (name "unconnected-(U$1-P3_3-Pad26)") (class "Default")
      (node (ref "U$1") (pin "26") (pinfunction "P3_3_26") (pintype "bidirectional"))
    )
    (net (code "77") (name "unconnected-(U$1-P3_4-Pad27)") (class "Default")
      (node (ref "U$1") (pin "27") (pinfunction "P3_4_27") (pintype "bidirectional"))
    )
    (net (code "78") (name "unconnected-(U$1-P3_6-Pad28)") (class "Default")
      (node (ref "U$1") (pin "28") (pinfunction "P3_6_28") (pintype "bidirectional"))
    )
    (net (code "79") (name "unconnected-(U$1-P3_7-Pad29)") (class "Default")
      (node (ref "U$1") (pin "29") (pinfunction "P3_7_29") (pintype "bidirectional"))
    )
    (net (code "80") (name "unconnected-(U$1-PMULDO_O-Pad10)") (class "Default")
      (node (ref "U$1") (pin "10") (pinfunction "PMULDO_O_10") (pintype "bidirectional"))
    )
    (net (code "81") (name "unconnected-(U$1-SW_BTN-Pad5)") (class "Default")
      (node (ref "U$1") (pin "5") (pinfunction "SW_BTN_5") (pintype "bidirectional"))
    )
    (net (code "82") (name "unconnected-(U$1-WAKEUP-Pad9)") (class "Default")
      (node (ref "U$1") (pin "9") (pinfunction "WAKEUP_9") (pintype "bidirectional"))
    )
    (net (code "83") (name "unconnected-(U1-NC-Pad4)") (class "Default")
      (node (ref "U1") (pin "4") (pinfunction "NC_4") (pintype "no_connect"))
    )
    (net (code "84") (name "unconnected-(U2-{slash}PG-Pad8)") (class "Default")
      (node (ref "U2") (pin "8") (pinfunction "/PG_8") (pintype "bidirectional"))
    )
    (net (code "85") (name "unconnected-(U4-NC-Pad4)") (class "Default")
      (node (ref "U4") (pin "4") (pinfunction "NC_4") (pintype "no_connect"))
    )
    (net (code "86") (name "unconnected-(U5-DEN_A{slash}G-Pad13)") (class "Default")
      (node (ref "U5") (pin "13") (pinfunction "DEN_A/G_13") (pintype "bidirectional"))
    )
    (net (code "87") (name "unconnected-(U5-DRDY_M-Pad9)") (class "Default")
      (node (ref "U5") (pin "9") (pinfunction "DRDY_M_9") (pintype "bidirectional"))
    )
    (net (code "88") (name "unconnected-(U5-INT1_A{slash}G-Pad11)") (class "Default")
      (node (ref "U5") (pin "11") (pinfunction "INT1_A/G_11") (pintype "bidirectional"))
    )
    (net (code "89") (name "unconnected-(U5-INT2_A{slash}G-Pad12)") (class "Default")
      (node (ref "U5") (pin "12") (pinfunction "INT2_A/G_12") (pintype "bidirectional"))
    )
    (net (code "90") (name "unconnected-(U5-INT_M-Pad10)") (class "Default")
      (node (ref "U5") (pin "10") (pinfunction "INT_M_10") (pintype "bidirectional"))
    )
    (net (code "91") (name "unconnected-(X2-Pad2)") (class "Default")
      (node (ref "X2") (pin "2") (pinfunction "2_2") (pintype "input"))
    )
    (net (code "92") (name "unconnected-(X2-Pad3)") (class "Default")
      (node (ref "X2") (pin "3") (pinfunction "3_3") (pintype "input"))
    )
    (net (code "93") (name "unconnected-(X2-Pad4)") (class "Default")
      (node (ref "X2") (pin "4") (pinfunction "4_4") (pintype "input"))
    )
  )
)
